# LED_Debug_-_CRBFH0.net
KiCad netlist of a schematic drawn in EAGLE
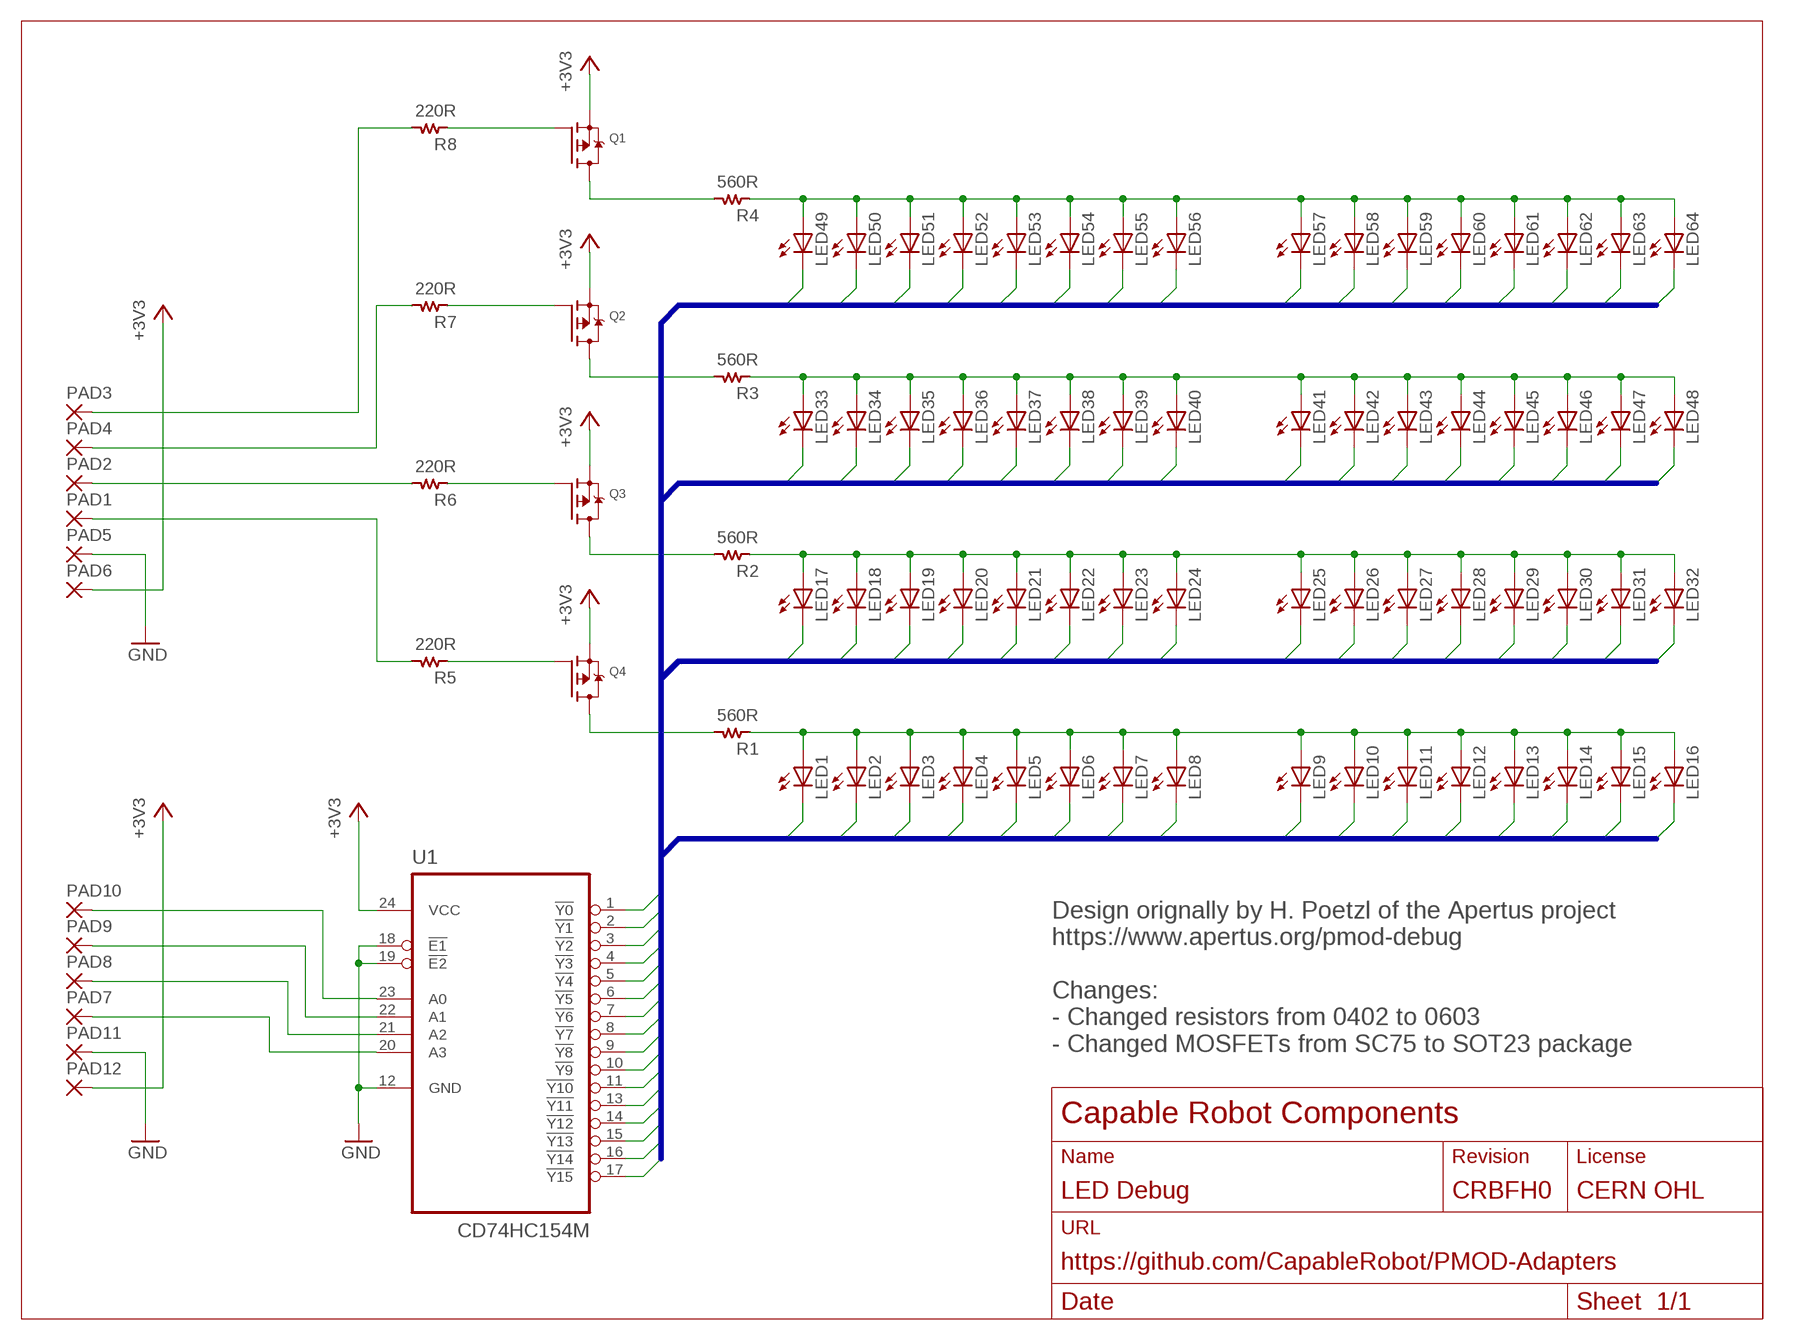
[diagram p0: schematic, sheet 1]

(export (version "E")
  (design (tool "Eeschema 10.0.6"))
  (components
    (comp (ref "LED1")
      (value "LEDCHIP-LED0603")
      (footprint "eagle-import:CHIP-LED0603")
      (libsource (lib "eagle-import") (part "LEDCHIP-LED0603"))
    )
    (comp (ref "LED2")
      (value "LEDCHIP-LED0603")
      (footprint "eagle-import:CHIP-LED0603")
      (libsource (lib "eagle-import") (part "LEDCHIP-LED0603"))
    )
    (comp (ref "LED3")
      (value "LEDCHIP-LED0603")
      (footprint "eagle-import:CHIP-LED0603")
      (libsource (lib "eagle-import") (part "LEDCHIP-LED0603"))
    )
    (comp (ref "LED4")
      (value "LEDCHIP-LED0603")
      (footprint "eagle-import:CHIP-LED0603")
      (libsource (lib "eagle-import") (part "LEDCHIP-LED0603"))
    )
    (comp (ref "LED5")
      (value "LEDCHIP-LED0603")
      (footprint "eagle-import:CHIP-LED0603")
      (libsource (lib "eagle-import") (part "LEDCHIP-LED0603"))
    )
    (comp (ref "LED6")
      (value "LEDCHIP-LED0603")
      (footprint "eagle-import:CHIP-LED0603")
      (libsource (lib "eagle-import") (part "LEDCHIP-LED0603"))
    )
    (comp (ref "LED7")
      (value "LEDCHIP-LED0603")
      (footprint "eagle-import:CHIP-LED0603")
      (libsource (lib "eagle-import") (part "LEDCHIP-LED0603"))
    )
    (comp (ref "LED8")
      (value "LEDCHIP-LED0603")
      (footprint "eagle-import:CHIP-LED0603")
      (libsource (lib "eagle-import") (part "LEDCHIP-LED0603"))
    )
    (comp (ref "LED9")
      (value "LEDCHIP-LED0603")
      (footprint "eagle-import:CHIP-LED0603")
      (libsource (lib "eagle-import") (part "LEDCHIP-LED0603"))
    )
    (comp (ref "LED10")
      (value "LEDCHIP-LED0603")
      (footprint "eagle-import:CHIP-LED0603")
      (libsource (lib "eagle-import") (part "LEDCHIP-LED0603"))
    )
    (comp (ref "LED11")
      (value "LEDCHIP-LED0603")
      (footprint "eagle-import:CHIP-LED0603")
      (libsource (lib "eagle-import") (part "LEDCHIP-LED0603"))
    )
    (comp (ref "LED12")
      (value "LEDCHIP-LED0603")
      (footprint "eagle-import:CHIP-LED0603")
      (libsource (lib "eagle-import") (part "LEDCHIP-LED0603"))
    )
    (comp (ref "LED13")
      (value "LEDCHIP-LED0603")
      (footprint "eagle-import:CHIP-LED0603")
      (libsource (lib "eagle-import") (part "LEDCHIP-LED0603"))
    )
    (comp (ref "LED14")
      (value "LEDCHIP-LED0603")
      (footprint "eagle-import:CHIP-LED0603")
      (libsource (lib "eagle-import") (part "LEDCHIP-LED0603"))
    )
    (comp (ref "LED15")
      (value "LEDCHIP-LED0603")
      (footprint "eagle-import:CHIP-LED0603")
      (libsource (lib "eagle-import") (part "LEDCHIP-LED0603"))
    )
    (comp (ref "LED16")
      (value "LEDCHIP-LED0603")
      (footprint "eagle-import:CHIP-LED0603")
      (libsource (lib "eagle-import") (part "LEDCHIP-LED0603"))
    )
    (comp (ref "LED17")
      (value "LEDCHIP-LED0603")
      (footprint "eagle-import:CHIP-LED0603")
      (libsource (lib "eagle-import") (part "LEDCHIP-LED0603"))
    )
    (comp (ref "LED18")
      (value "LEDCHIP-LED0603")
      (footprint "eagle-import:CHIP-LED0603")
      (libsource (lib "eagle-import") (part "LEDCHIP-LED0603"))
    )
    (comp (ref "LED19")
      (value "LEDCHIP-LED0603")
      (footprint "eagle-import:CHIP-LED0603")
      (libsource (lib "eagle-import") (part "LEDCHIP-LED0603"))
    )
    (comp (ref "LED20")
      (value "LEDCHIP-LED0603")
      (footprint "eagle-import:CHIP-LED0603")
      (libsource (lib "eagle-import") (part "LEDCHIP-LED0603"))
    )
    (comp (ref "LED21")
      (value "LEDCHIP-LED0603")
      (footprint "eagle-import:CHIP-LED0603")
      (libsource (lib "eagle-import") (part "LEDCHIP-LED0603"))
    )
    (comp (ref "LED22")
      (value "LEDCHIP-LED0603")
      (footprint "eagle-import:CHIP-LED0603")
      (libsource (lib "eagle-import") (part "LEDCHIP-LED0603"))
    )
    (comp (ref "LED23")
      (value "LEDCHIP-LED0603")
      (footprint "eagle-import:CHIP-LED0603")
      (libsource (lib "eagle-import") (part "LEDCHIP-LED0603"))
    )
    (comp (ref "LED24")
      (value "LEDCHIP-LED0603")
      (footprint "eagle-import:CHIP-LED0603")
      (libsource (lib "eagle-import") (part "LEDCHIP-LED0603"))
    )
    (comp (ref "LED25")
      (value "LEDCHIP-LED0603")
      (footprint "eagle-import:CHIP-LED0603")
      (libsource (lib "eagle-import") (part "LEDCHIP-LED0603"))
    )
    (comp (ref "LED26")
      (value "LEDCHIP-LED0603")
      (footprint "eagle-import:CHIP-LED0603")
      (libsource (lib "eagle-import") (part "LEDCHIP-LED0603"))
    )
    (comp (ref "LED27")
      (value "LEDCHIP-LED0603")
      (footprint "eagle-import:CHIP-LED0603")
      (libsource (lib "eagle-import") (part "LEDCHIP-LED0603"))
    )
    (comp (ref "LED28")
      (value "LEDCHIP-LED0603")
      (footprint "eagle-import:CHIP-LED0603")
      (libsource (lib "eagle-import") (part "LEDCHIP-LED0603"))
    )
    (comp (ref "LED29")
      (value "LEDCHIP-LED0603")
      (footprint "eagle-import:CHIP-LED0603")
      (libsource (lib "eagle-import") (part "LEDCHIP-LED0603"))
    )
    (comp (ref "LED30")
      (value "LEDCHIP-LED0603")
      (footprint "eagle-import:CHIP-LED0603")
      (libsource (lib "eagle-import") (part "LEDCHIP-LED0603"))
    )
    (comp (ref "LED31")
      (value "LEDCHIP-LED0603")
      (footprint "eagle-import:CHIP-LED0603")
      (libsource (lib "eagle-import") (part "LEDCHIP-LED0603"))
    )
    (comp (ref "LED32")
      (value "LEDCHIP-LED0603")
      (footprint "eagle-import:CHIP-LED0603")
      (libsource (lib "eagle-import") (part "LEDCHIP-LED0603"))
    )
    (comp (ref "LED33")
      (value "LEDCHIP-LED0603")
      (footprint "eagle-import:CHIP-LED0603")
      (libsource (lib "eagle-import") (part "LEDCHIP-LED0603"))
    )
    (comp (ref "LED34")
      (value "LEDCHIP-LED0603")
      (footprint "eagle-import:CHIP-LED0603")
      (libsource (lib "eagle-import") (part "LEDCHIP-LED0603"))
    )
    (comp (ref "LED35")
      (value "LEDCHIP-LED0603")
      (footprint "eagle-import:CHIP-LED0603")
      (libsource (lib "eagle-import") (part "LEDCHIP-LED0603"))
    )
    (comp (ref "LED36")
      (value "LEDCHIP-LED0603")
      (footprint "eagle-import:CHIP-LED0603")
      (libsource (lib "eagle-import") (part "LEDCHIP-LED0603"))
    )
    (comp (ref "LED37")
      (value "LEDCHIP-LED0603")
      (footprint "eagle-import:CHIP-LED0603")
      (libsource (lib "eagle-import") (part "LEDCHIP-LED0603"))
    )
    (comp (ref "LED38")
      (value "LEDCHIP-LED0603")
      (footprint "eagle-import:CHIP-LED0603")
      (libsource (lib "eagle-import") (part "LEDCHIP-LED0603"))
    )
    (comp (ref "LED39")
      (value "LEDCHIP-LED0603")
      (footprint "eagle-import:CHIP-LED0603")
      (libsource (lib "eagle-import") (part "LEDCHIP-LED0603"))
    )
    (comp (ref "LED40")
      (value "LEDCHIP-LED0603")
      (footprint "eagle-import:CHIP-LED0603")
      (libsource (lib "eagle-import") (part "LEDCHIP-LED0603"))
    )
    (comp (ref "LED41")
      (value "LEDCHIP-LED0603")
      (footprint "eagle-import:CHIP-LED0603")
      (libsource (lib "eagle-import") (part "LEDCHIP-LED0603"))
    )
    (comp (ref "LED42")
      (value "LEDCHIP-LED0603")
      (footprint "eagle-import:CHIP-LED0603")
      (libsource (lib "eagle-import") (part "LEDCHIP-LED0603"))
    )
    (comp (ref "LED43")
      (value "LEDCHIP-LED0603")
      (footprint "eagle-import:CHIP-LED0603")
      (libsource (lib "eagle-import") (part "LEDCHIP-LED0603"))
    )
    (comp (ref "LED44")
      (value "LEDCHIP-LED0603")
      (footprint "eagle-import:CHIP-LED0603")
      (libsource (lib "eagle-import") (part "LEDCHIP-LED0603"))
    )
    (comp (ref "LED45")
      (value "LEDCHIP-LED0603")
      (footprint "eagle-import:CHIP-LED0603")
      (libsource (lib "eagle-import") (part "LEDCHIP-LED0603"))
    )
    (comp (ref "LED46")
      (value "LEDCHIP-LED0603")
      (footprint "eagle-import:CHIP-LED0603")
      (libsource (lib "eagle-import") (part "LEDCHIP-LED0603"))
    )
    (comp (ref "LED47")
      (value "LEDCHIP-LED0603")
      (footprint "eagle-import:CHIP-LED0603")
      (libsource (lib "eagle-import") (part "LEDCHIP-LED0603"))
    )
    (comp (ref "LED48")
      (value "LEDCHIP-LED0603")
      (footprint "eagle-import:CHIP-LED0603")
      (libsource (lib "eagle-import") (part "LEDCHIP-LED0603"))
    )
    (comp (ref "LED49")
      (value "LEDCHIP-LED0603")
      (footprint "eagle-import:CHIP-LED0603")
      (libsource (lib "eagle-import") (part "LEDCHIP-LED0603"))
    )
    (comp (ref "LED50")
      (value "LEDCHIP-LED0603")
      (footprint "eagle-import:CHIP-LED0603")
      (libsource (lib "eagle-import") (part "LEDCHIP-LED0603"))
    )
    (comp (ref "LED51")
      (value "LEDCHIP-LED0603")
      (footprint "eagle-import:CHIP-LED0603")
      (libsource (lib "eagle-import") (part "LEDCHIP-LED0603"))
    )
    (comp (ref "LED52")
      (value "LEDCHIP-LED0603")
      (footprint "eagle-import:CHIP-LED0603")
      (libsource (lib "eagle-import") (part "LEDCHIP-LED0603"))
    )
    (comp (ref "LED53")
      (value "LEDCHIP-LED0603")
      (footprint "eagle-import:CHIP-LED0603")
      (libsource (lib "eagle-import") (part "LEDCHIP-LED0603"))
    )
    (comp (ref "LED54")
      (value "LEDCHIP-LED0603")
      (footprint "eagle-import:CHIP-LED0603")
      (libsource (lib "eagle-import") (part "LEDCHIP-LED0603"))
    )
    (comp (ref "LED55")
      (value "LEDCHIP-LED0603")
      (footprint "eagle-import:CHIP-LED0603")
      (libsource (lib "eagle-import") (part "LEDCHIP-LED0603"))
    )
    (comp (ref "LED56")
      (value "LEDCHIP-LED0603")
      (footprint "eagle-import:CHIP-LED0603")
      (libsource (lib "eagle-import") (part "LEDCHIP-LED0603"))
    )
    (comp (ref "LED57")
      (value "LEDCHIP-LED0603")
      (footprint "eagle-import:CHIP-LED0603")
      (libsource (lib "eagle-import") (part "LEDCHIP-LED0603"))
    )
    (comp (ref "LED58")
      (value "LEDCHIP-LED0603")
      (footprint "eagle-import:CHIP-LED0603")
      (libsource (lib "eagle-import") (part "LEDCHIP-LED0603"))
    )
    (comp (ref "LED59")
      (value "LEDCHIP-LED0603")
      (footprint "eagle-import:CHIP-LED0603")
      (libsource (lib "eagle-import") (part "LEDCHIP-LED0603"))
    )
    (comp (ref "LED60")
      (value "LEDCHIP-LED0603")
      (footprint "eagle-import:CHIP-LED0603")
      (libsource (lib "eagle-import") (part "LEDCHIP-LED0603"))
    )
    (comp (ref "LED61")
      (value "LEDCHIP-LED0603")
      (footprint "eagle-import:CHIP-LED0603")
      (libsource (lib "eagle-import") (part "LEDCHIP-LED0603"))
    )
    (comp (ref "LED62")
      (value "LEDCHIP-LED0603")
      (footprint "eagle-import:CHIP-LED0603")
      (libsource (lib "eagle-import") (part "LEDCHIP-LED0603"))
    )
    (comp (ref "LED63")
      (value "LEDCHIP-LED0603")
      (footprint "eagle-import:CHIP-LED0603")
      (libsource (lib "eagle-import") (part "LEDCHIP-LED0603"))
    )
    (comp (ref "LED64")
      (value "LEDCHIP-LED0603")
      (footprint "eagle-import:CHIP-LED0603")
      (libsource (lib "eagle-import") (part "LEDCHIP-LED0603"))
    )
    (comp (ref "PAD1")
      (value "SMD2HR")
      (footprint "eagle-import:SMD1.27-3.175HR")
      (libsource (lib "eagle-import") (part "SMD2HR"))
    )
    (comp (ref "PAD2")
      (value "SMD2HR")
      (footprint "eagle-import:SMD1.27-3.175HR")
      (libsource (lib "eagle-import") (part "SMD2HR"))
    )
    (comp (ref "PAD3")
      (value "SMD2HR")
      (footprint "eagle-import:SMD1.27-3.175HR")
      (libsource (lib "eagle-import") (part "SMD2HR"))
    )
    (comp (ref "PAD4")
      (value "SMD2HR")
      (footprint "eagle-import:SMD1.27-3.175HR")
      (libsource (lib "eagle-import") (part "SMD2HR"))
    )
    (comp (ref "PAD5")
      (value "SMD2HR")
      (footprint "eagle-import:SMD1.27-3.175HR")
      (libsource (lib "eagle-import") (part "SMD2HR"))
    )
    (comp (ref "PAD6")
      (value "SMD2HR")
      (footprint "eagle-import:SMD1.27-3.175HR")
      (libsource (lib "eagle-import") (part "SMD2HR"))
    )
    (comp (ref "PAD7")
      (value "SMD2HR")
      (footprint "eagle-import:SMD1.27-3.175HR")
      (libsource (lib "eagle-import") (part "SMD2HR"))
    )
    (comp (ref "PAD8")
      (value "SMD2HR")
      (footprint "eagle-import:SMD1.27-3.175HR")
      (libsource (lib "eagle-import") (part "SMD2HR"))
    )
    (comp (ref "PAD9")
      (value "SMD2HR")
      (footprint "eagle-import:SMD1.27-3.175HR")
      (libsource (lib "eagle-import") (part "SMD2HR"))
    )
    (comp (ref "PAD10")
      (value "SMD2HR")
      (footprint "eagle-import:SMD1.27-3.175HR")
      (libsource (lib "eagle-import") (part "SMD2HR"))
    )
    (comp (ref "PAD11")
      (value "SMD2HR")
      (footprint "eagle-import:SMD1.27-3.175HR")
      (libsource (lib "eagle-import") (part "SMD2HR"))
    )
    (comp (ref "PAD12")
      (value "SMD2HR")
      (footprint "eagle-import:SMD1.27-3.175HR")
      (libsource (lib "eagle-import") (part "SMD2HR"))
    )
    (comp (ref "Q1")
      (value "MOSFET-P")
      (footprint "eagle-import:SOT23-R")
      (libsource (lib "eagle-import") (part "MOSFET-P"))
    )
    (comp (ref "Q2")
      (value "MOSFET-P")
      (footprint "eagle-import:SOT23-R")
      (libsource (lib "eagle-import") (part "MOSFET-P"))
    )
    (comp (ref "Q3")
      (value "MOSFET-P")
      (footprint "eagle-import:SOT23-R")
      (libsource (lib "eagle-import") (part "MOSFET-P"))
    )
    (comp (ref "Q4")
      (value "MOSFET-P")
      (footprint "eagle-import:SOT23-R")
      (libsource (lib "eagle-import") (part "MOSFET-P"))
    )
    (comp (ref "R1")
      (value "560R")
      (footprint "eagle-import:0603")
      (libsource (lib "eagle-import") (part "RES0603"))
    )
    (comp (ref "R2")
      (value "560R")
      (footprint "eagle-import:0603")
      (libsource (lib "eagle-import") (part "RES0603"))
    )
    (comp (ref "R3")
      (value "560R")
      (footprint "eagle-import:0603")
      (libsource (lib "eagle-import") (part "RES0603"))
    )
    (comp (ref "R4")
      (value "560R")
      (footprint "eagle-import:0603")
      (libsource (lib "eagle-import") (part "RES0603"))
    )
    (comp (ref "R5")
      (value "220R")
      (footprint "eagle-import:0603")
      (libsource (lib "eagle-import") (part "RES0603"))
    )
    (comp (ref "R6")
      (value "220R")
      (footprint "eagle-import:0603")
      (libsource (lib "eagle-import") (part "RES0603"))
    )
    (comp (ref "R7")
      (value "220R")
      (footprint "eagle-import:0603")
      (libsource (lib "eagle-import") (part "RES0603"))
    )
    (comp (ref "R8")
      (value "220R")
      (footprint "eagle-import:0603")
      (libsource (lib "eagle-import") (part "RES0603"))
    )
    (comp (ref "U1")
      (value "CD74HC154M")
      (footprint "eagle-import:SOIC127P1030X265-24N")
      (libsource (lib "eagle-import") (part "CD74HC154M"))
    )
  )
  (nets
    (net (code "1") (name "+3V3") (class "Default")
      (node (ref "PAD12") (pin "1") (pinfunction "P_1") (pintype "passive"))
      (node (ref "PAD6") (pin "1") (pinfunction "P_1") (pintype "passive"))
      (node (ref "Q1") (pin "2") (pinfunction "S_2") (pintype "passive"))
      (node (ref "Q2") (pin "2") (pinfunction "S_2") (pintype "passive"))
      (node (ref "Q3") (pin "2") (pinfunction "S_2") (pintype "passive"))
      (node (ref "Q4") (pin "2") (pinfunction "S_2") (pintype "passive"))
      (node (ref "U1") (pin "24") (pinfunction "VCC_24") (pintype "power_in"))
    )
    (net (code "2") (name "/C0") (class "Default")
      (node (ref "LED1") (pin "C") (pinfunction "C_C") (pintype "passive"))
      (node (ref "LED17") (pin "C") (pinfunction "C_C") (pintype "passive"))
      (node (ref "LED33") (pin "C") (pinfunction "C_C") (pintype "passive"))
      (node (ref "LED49") (pin "C") (pinfunction "C_C") (pintype "passive"))
      (node (ref "U1") (pin "1") (pinfunction "~{Y0}_1") (pintype "output"))
    )
    (net (code "3") (name "/C1") (class "Default")
      (node (ref "LED18") (pin "C") (pinfunction "C_C") (pintype "passive"))
      (node (ref "LED2") (pin "C") (pinfunction "C_C") (pintype "passive"))
      (node (ref "LED34") (pin "C") (pinfunction "C_C") (pintype "passive"))
      (node (ref "LED50") (pin "C") (pinfunction "C_C") (pintype "passive"))
      (node (ref "U1") (pin "2") (pinfunction "~{Y1}_2") (pintype "output"))
    )
    (net (code "4") (name "/C2") (class "Default")
      (node (ref "LED19") (pin "C") (pinfunction "C_C") (pintype "passive"))
      (node (ref "LED3") (pin "C") (pinfunction "C_C") (pintype "passive"))
      (node (ref "LED35") (pin "C") (pinfunction "C_C") (pintype "passive"))
      (node (ref "LED51") (pin "C") (pinfunction "C_C") (pintype "passive"))
      (node (ref "U1") (pin "3") (pinfunction "~{Y2}_3") (pintype "output"))
    )
    (net (code "5") (name "/C3") (class "Default")
      (node (ref "LED20") (pin "C") (pinfunction "C_C") (pintype "passive"))
      (node (ref "LED36") (pin "C") (pinfunction "C_C") (pintype "passive"))
      (node (ref "LED4") (pin "C") (pinfunction "C_C") (pintype "passive"))
      (node (ref "LED52") (pin "C") (pinfunction "C_C") (pintype "passive"))
      (node (ref "U1") (pin "4") (pinfunction "~{Y3}_4") (pintype "output"))
    )
    (net (code "6") (name "/C4") (class "Default")
      (node (ref "LED21") (pin "C") (pinfunction "C_C") (pintype "passive"))
      (node (ref "LED37") (pin "C") (pinfunction "C_C") (pintype "passive"))
      (node (ref "LED5") (pin "C") (pinfunction "C_C") (pintype "passive"))
      (node (ref "LED53") (pin "C") (pinfunction "C_C") (pintype "passive"))
      (node (ref "U1") (pin "5") (pinfunction "~{Y4}_5") (pintype "output"))
    )
    (net (code "7") (name "/C5") (class "Default")
      (node (ref "LED22") (pin "C") (pinfunction "C_C") (pintype "passive"))
      (node (ref "LED38") (pin "C") (pinfunction "C_C") (pintype "passive"))
      (node (ref "LED54") (pin "C") (pinfunction "C_C") (pintype "passive"))
      (node (ref "LED6") (pin "C") (pinfunction "C_C") (pintype "passive"))
      (node (ref "U1") (pin "6") (pinfunction "~{Y5}_6") (pintype "output"))
    )
    (net (code "8") (name "/C6") (class "Default")
      (node (ref "LED23") (pin "C") (pinfunction "C_C") (pintype "passive"))
      (node (ref "LED39") (pin "C") (pinfunction "C_C") (pintype "passive"))
      (node (ref "LED55") (pin "C") (pinfunction "C_C") (pintype "passive"))
      (node (ref "LED7") (pin "C") (pinfunction "C_C") (pintype "passive"))
      (node (ref "U1") (pin "7") (pinfunction "~{Y6}_7") (pintype "output"))
    )
    (net (code "9") (name "/C7") (class "Default")
      (node (ref "LED24") (pin "C") (pinfunction "C_C") (pintype "passive"))
      (node (ref "LED40") (pin "C") (pinfunction "C_C") (pintype "passive"))
      (node (ref "LED56") (pin "C") (pinfunction "C_C") (pintype "passive"))
      (node (ref "LED8") (pin "C") (pinfunction "C_C") (pintype "passive"))
      (node (ref "U1") (pin "8") (pinfunction "~{Y7}_8") (pintype "output"))
    )
    (net (code "10") (name "/C8") (class "Default")
      (node (ref "LED25") (pin "C") (pinfunction "C_C") (pintype "passive"))
      (node (ref "LED41") (pin "C") (pinfunction "C_C") (pintype "passive"))
      (node (ref "LED57") (pin "C") (pinfunction "C_C") (pintype "passive"))
      (node (ref "LED9") (pin "C") (pinfunction "C_C") (pintype "passive"))
      (node (ref "U1") (pin "9") (pinfunction "~{Y8}_9") (pintype "output"))
    )
    (net (code "11") (name "/C9") (class "Default")
      (node (ref "LED10") (pin "C") (pinfunction "C_C") (pintype "passive"))
      (node (ref "LED26") (pin "C") (pinfunction "C_C") (pintype "passive"))
      (node (ref "LED42") (pin "C") (pinfunction "C_C") (pintype "passive"))
      (node (ref "LED58") (pin "C") (pinfunction "C_C") (pintype "passive"))
      (node (ref "U1") (pin "10") (pinfunction "~{Y9}_10") (pintype "output"))
    )
    (net (code "12") (name "/C10") (class "Default")
      (node (ref "LED11") (pin "C") (pinfunction "C_C") (pintype "passive"))
      (node (ref "LED27") (pin "C") (pinfunction "C_C") (pintype "passive"))
      (node (ref "LED43") (pin "C") (pinfunction "C_C") (pintype "passive"))
      (node (ref "LED59") (pin "C") (pinfunction "C_C") (pintype "passive"))
      (node (ref "U1") (pin "11") (pinfunction "~{Y10}_11") (pintype "output"))
    )
    (net (code "13") (name "/C11") (class "Default")
      (node (ref "LED12") (pin "C") (pinfunction "C_C") (pintype "passive"))
      (node (ref "LED28") (pin "C") (pinfunction "C_C") (pintype "passive"))
      (node (ref "LED44") (pin "C") (pinfunction "C_C") (pintype "passive"))
      (node (ref "LED60") (pin "C") (pinfunction "C_C") (pintype "passive"))
      (node (ref "U1") (pin "13") (pinfunction "~{Y11}_13") (pintype "output"))
    )
    (net (code "14") (name "/C12") (class "Default")
      (node (ref "LED13") (pin "C") (pinfunction "C_C") (pintype "passive"))
      (node (ref "LED29") (pin "C") (pinfunction "C_C") (pintype "passive"))
      (node (ref "LED45") (pin "C") (pinfunction "C_C") (pintype "passive"))
      (node (ref "LED61") (pin "C") (pinfunction "C_C") (pintype "passive"))
      (node (ref "U1") (pin "14") (pinfunction "~{Y12}_14") (pintype "output"))
    )
    (net (code "15") (name "/C13") (class "Default")
      (node (ref "LED14") (pin "C") (pinfunction "C_C") (pintype "passive"))
      (node (ref "LED30") (pin "C") (pinfunction "C_C") (pintype "passive"))
      (node (ref "LED46") (pin "C") (pinfunction "C_C") (pintype "passive"))
      (node (ref "LED62") (pin "C") (pinfunction "C_C") (pintype "passive"))
      (node (ref "U1") (pin "15") (pinfunction "~{Y13}_15") (pintype "output"))
    )
    (net (code "16") (name "/C14") (class "Default")
      (node (ref "LED15") (pin "C") (pinfunction "C_C") (pintype "passive"))
      (node (ref "LED31") (pin "C") (pinfunction "C_C") (pintype "passive"))
      (node (ref "LED47") (pin "C") (pinfunction "C_C") (pintype "passive"))
      (node (ref "LED63") (pin "C") (pinfunction "C_C") (pintype "passive"))
      (node (ref "U1") (pin "16") (pinfunction "~{Y14}_16") (pintype "output"))
    )
    (net (code "17") (name "/C15") (class "Default")
      (node (ref "LED16") (pin "C") (pinfunction "C_C") (pintype "passive"))
      (node (ref "LED32") (pin "C") (pinfunction "C_C") (pintype "passive"))
      (node (ref "LED48") (pin "C") (pinfunction "C_C") (pintype "passive"))
      (node (ref "LED64") (pin "C") (pinfunction "C_C") (pintype "passive"))
      (node (ref "U1") (pin "17") (pinfunction "~{Y15}_17") (pintype "output"))
    )
    (net (code "18") (name "GND") (class "Default")
      (node (ref "PAD11") (pin "1") (pinfunction "P_1") (pintype "passive"))
      (node (ref "PAD5") (pin "1") (pinfunction "P_1") (pintype "passive"))
      (node (ref "U1") (pin "12") (pinfunction "GND_12") (pintype "passive"))
      (node (ref "U1") (pin "18") (pinfunction "~{E1}_18") (pintype "input"))
      (node (ref "U1") (pin "19") (pinfunction "~{E2}_19") (pintype "input"))
    )
    (net (code "19") (name "Net-(LED1-PadA)") (class "Default")
      (node (ref "LED1") (pin "A") (pinfunction "A_A") (pintype "passive"))
      (node (ref "LED10") (pin "A") (pinfunction "A_A") (pintype "passive"))
      (node (ref "LED11") (pin "A") (pinfunction "A_A") (pintype "passive"))
      (node (ref "LED12") (pin "A") (pinfunction "A_A") (pintype "passive"))
      (node (ref "LED13") (pin "A") (pinfunction "A_A") (pintype "passive"))
      (node (ref "LED14") (pin "A") (pinfunction "A_A") (pintype "passive"))
      (node (ref "LED15") (pin "A") (pinfunction "A_A") (pintype "passive"))
      (node (ref "LED16") (pin "A") (pinfunction "A_A") (pintype "passive"))
      (node (ref "LED2") (pin "A") (pinfunction "A_A") (pintype "passive"))
      (node (ref "LED3") (pin "A") (pinfunction "A_A") (pintype "passive"))
      (node (ref "LED4") (pin "A") (pinfunction "A_A") (pintype "passive"))
      (node (ref "LED5") (pin "A") (pinfunction "A_A") (pintype "passive"))
      (node (ref "LED6") (pin "A") (pinfunction "A_A") (pintype "passive"))
      (node (ref "LED7") (pin "A") (pinfunction "A_A") (pintype "passive"))
      (node (ref "LED8") (pin "A") (pinfunction "A_A") (pintype "passive"))
      (node (ref "LED9") (pin "A") (pinfunction "A_A") (pintype "passive"))
      (node (ref "R1") (pin "1") (pinfunction "1_1") (pintype "passive"))
    )
    (net (code "20") (name "Net-(LED17-PadA)") (class "Default")
      (node (ref "LED17") (pin "A") (pinfunction "A_A") (pintype "passive"))
      (node (ref "LED18") (pin "A") (pinfunction "A_A") (pintype "passive"))
      (node (ref "LED19") (pin "A") (pinfunction "A_A") (pintype "passive"))
      (node (ref "LED20") (pin "A") (pinfunction "A_A") (pintype "passive"))
      (node (ref "LED21") (pin "A") (pinfunction "A_A") (pintype "passive"))
      (node (ref "LED22") (pin "A") (pinfunction "A_A") (pintype "passive"))
      (node (ref "LED23") (pin "A") (pinfunction "A_A") (pintype "passive"))
      (node (ref "LED24") (pin "A") (pinfunction "A_A") (pintype "passive"))
      (node (ref "LED25") (pin "A") (pinfunction "A_A") (pintype "passive"))
      (node (ref "LED26") (pin "A") (pinfunction "A_A") (pintype "passive"))
      (node (ref "LED27") (pin "A") (pinfunction "A_A") (pintype "passive"))
      (node (ref "LED28") (pin "A") (pinfunction "A_A") (pintype "passive"))
      (node (ref "LED29") (pin "A") (pinfunction "A_A") (pintype "passive"))
      (node (ref "LED30") (pin "A") (pinfunction "A_A") (pintype "passive"))
      (node (ref "LED31") (pin "A") (pinfunction "A_A") (pintype "passive"))
      (node (ref "LED32") (pin "A") (pinfunction "A_A") (pintype "passive"))
      (node (ref "R2") (pin "1") (pinfunction "1_1") (pintype "passive"))
    )
    (net (code "21") (name "Net-(LED33-PadA)") (class "Default")
      (node (ref "LED33") (pin "A") (pinfunction "A_A") (pintype "passive"))
      (node (ref "LED34") (pin "A") (pinfunction "A_A") (pintype "passive"))
      (node (ref "LED35") (pin "A") (pinfunction "A_A") (pintype "passive"))
      (node (ref "LED36") (pin "A") (pinfunction "A_A") (pintype "passive"))
      (node (ref "LED37") (pin "A") (pinfunction "A_A") (pintype "passive"))
      (node (ref "LED38") (pin "A") (pinfunction "A_A") (pintype "passive"))
      (node (ref "LED39") (pin "A") (pinfunction "A_A") (pintype "passive"))
      (node (ref "LED40") (pin "A") (pinfunction "A_A") (pintype "passive"))
      (node (ref "LED41") (pin "A") (pinfunction "A_A") (pintype "passive"))
      (node (ref "LED42") (pin "A") (pinfunction "A_A") (pintype "passive"))
      (node (ref "LED43") (pin "A") (pinfunction "A_A") (pintype "passive"))
      (node (ref "LED44") (pin "A") (pinfunction "A_A") (pintype "passive"))
      (node (ref "LED45") (pin "A") (pinfunction "A_A") (pintype "passive"))
      (node (ref "LED46") (pin "A") (pinfunction "A_A") (pintype "passive"))
      (node (ref "LED47") (pin "A") (pinfunction "A_A") (pintype "passive"))
      (node (ref "LED48") (pin "A") (pinfunction "A_A") (pintype "passive"))
      (node (ref "R3") (pin "1") (pinfunction "1_1") (pintype "passive"))
    )
    (net (code "22") (name "Net-(LED49-PadA)") (class "Default")
      (node (ref "LED49") (pin "A") (pinfunction "A_A") (pintype "passive"))
      (node (ref "LED50") (pin "A") (pinfunction "A_A") (pintype "passive"))
      (node (ref "LED51") (pin "A") (pinfunction "A_A") (pintype "passive"))
      (node (ref "LED52") (pin "A") (pinfunction "A_A") (pintype "passive"))
      (node (ref "LED53") (pin "A") (pinfunction "A_A") (pintype "passive"))
      (node (ref "LED54") (pin "A") (pinfunction "A_A") (pintype "passive"))
      (node (ref "LED55") (pin "A") (pinfunction "A_A") (pintype "passive"))
      (node (ref "LED56") (pin "A") (pinfunction "A_A") (pintype "passive"))
      (node (ref "LED57") (pin "A") (pinfunction "A_A") (pintype "passive"))
      (node (ref "LED58") (pin "A") (pinfunction "A_A") (pintype "passive"))
      (node (ref "LED59") (pin "A") (pinfunction "A_A") (pintype "passive"))
      (node (ref "LED60") (pin "A") (pinfunction "A_A") (pintype "passive"))
      (node (ref "LED61") (pin "A") (pinfunction "A_A") (pintype "passive"))
      (node (ref "LED62") (pin "A") (pinfunction "A_A") (pintype "passive"))
      (node (ref "LED63") (pin "A") (pinfunction "A_A") (pintype "passive"))
      (node (ref "LED64") (pin "A") (pinfunction "A_A") (pintype "passive"))
      (node (ref "R4") (pin "1") (pinfunction "1_1") (pintype "passive"))
    )
    (net (code "23") (name "Net-(PAD1-P)") (class "Default")
      (node (ref "PAD1") (pin "1") (pinfunction "P_1") (pintype "passive"))
      (node (ref "R5") (pin "2") (pinfunction "2_2") (pintype "passive"))
    )
    (net (code "24") (name "Net-(PAD2-P)") (class "Default")
      (node (ref "PAD2") (pin "1") (pinfunction "P_1") (pintype "passive"))
      (node (ref "R6") (pin "2") (pinfunction "2_2") (pintype "passive"))
    )
    (net (code "25") (name "Net-(PAD3-P)") (class "Default")
      (node (ref "PAD3") (pin "1") (pinfunction "P_1") (pintype "passive"))
      (node (ref "R8") (pin "2") (pinfunction "2_2") (pintype "passive"))
    )
    (net (code "26") (name "Net-(PAD4-P)") (class "Default")
      (node (ref "PAD4") (pin "1") (pinfunction "P_1") (pintype "passive"))
      (node (ref "R7") (pin "2") (pinfunction "2_2") (pintype "passive"))
    )
    (net (code "27") (name "Net-(PAD7-P)") (class "Default")
      (node (ref "PAD7") (pin "1") (pinfunction "P_1") (pintype "passive"))
      (node (ref "U1") (pin "20") (pinfunction "A3_20") (pintype "input"))
    )
    (net (code "28") (name "Net-(PAD8-P)") (class "Default")
      (node (ref "PAD8") (pin "1") (pinfunction "P_1") (pintype "passive"))
      (node (ref "U1") (pin "21") (pinfunction "A2_21") (pintype "input"))
    )
    (net (code "29") (name "Net-(PAD9-P)") (class "Default")
      (node (ref "PAD9") (pin "1") (pinfunction "P_1") (pintype "passive"))
      (node (ref "U1") (pin "22") (pinfunction "A1_22") (pintype "input"))
    )
    (net (code "30") (name "Net-(PAD10-P)") (class "Default")
      (node (ref "PAD10") (pin "1") (pinfunction "P_1") (pintype "passive"))
      (node (ref "U1") (pin "23") (pinfunction "A0_23") (pintype "input"))
    )
    (net (code "31") (name "Net-(Q1-D)") (class "Default")
      (node (ref "Q1") (pin "3") (pinfunction "D_3") (pintype "passive"))
      (node (ref "R4") (pin "2") (pinfunction "2_2") (pintype "passive"))
    )
    (net (code "32") (name "Net-(Q1-G)") (class "Default")
      (node (ref "Q1") (pin "1") (pinfunction "G_1") (pintype "passive"))
      (node (ref "R8") (pin "1") (pinfunction "1_1") (pintype "passive"))
    )
    (net (code "33") (name "Net-(Q2-D)") (class "Default")
      (node (ref "Q2") (pin "3") (pinfunction "D_3") (pintype "passive"))
      (node (ref "R3") (pin "2") (pinfunction "2_2") (pintype "passive"))
    )
    (net (code "34") (name "Net-(Q2-G)") (class "Default")
      (node (ref "Q2") (pin "1") (pinfunction "G_1") (pintype "passive"))
      (node (ref "R7") (pin "1") (pinfunction "1_1") (pintype "passive"))
    )
    (net (code "35") (name "Net-(Q3-D)") (class "Default")
      (node (ref "Q3") (pin "3") (pinfunction "D_3") (pintype "passive"))
      (node (ref "R2") (pin "2") (pinfunction "2_2") (pintype "passive"))
    )
    (net (code "36") (name "Net-(Q3-G)") (class "Default")
      (node (ref "Q3") (pin "1") (pinfunction "G_1") (pintype "passive"))
      (node (ref "R6") (pin "1") (pinfunction "1_1") (pintype "passive"))
    )
    (net (code "37") (name "Net-(Q4-D)") (class "Default")
      (node (ref "Q4") (pin "3") (pinfunction "D_3") (pintype "passive"))
      (node (ref "R1") (pin "2") (pinfunction "2_2") (pintype "passive"))
    )
    (net (code "38") (name "Net-(Q4-G)") (class "Default")
      (node (ref "Q4") (pin "1") (pinfunction "G_1") (pintype "passive"))
      (node (ref "R5") (pin "1") (pinfunction "1_1") (pintype "passive"))
    )
  )
)
